# W032B.net
KiCad netlist of a schematic drawn in EAGLE
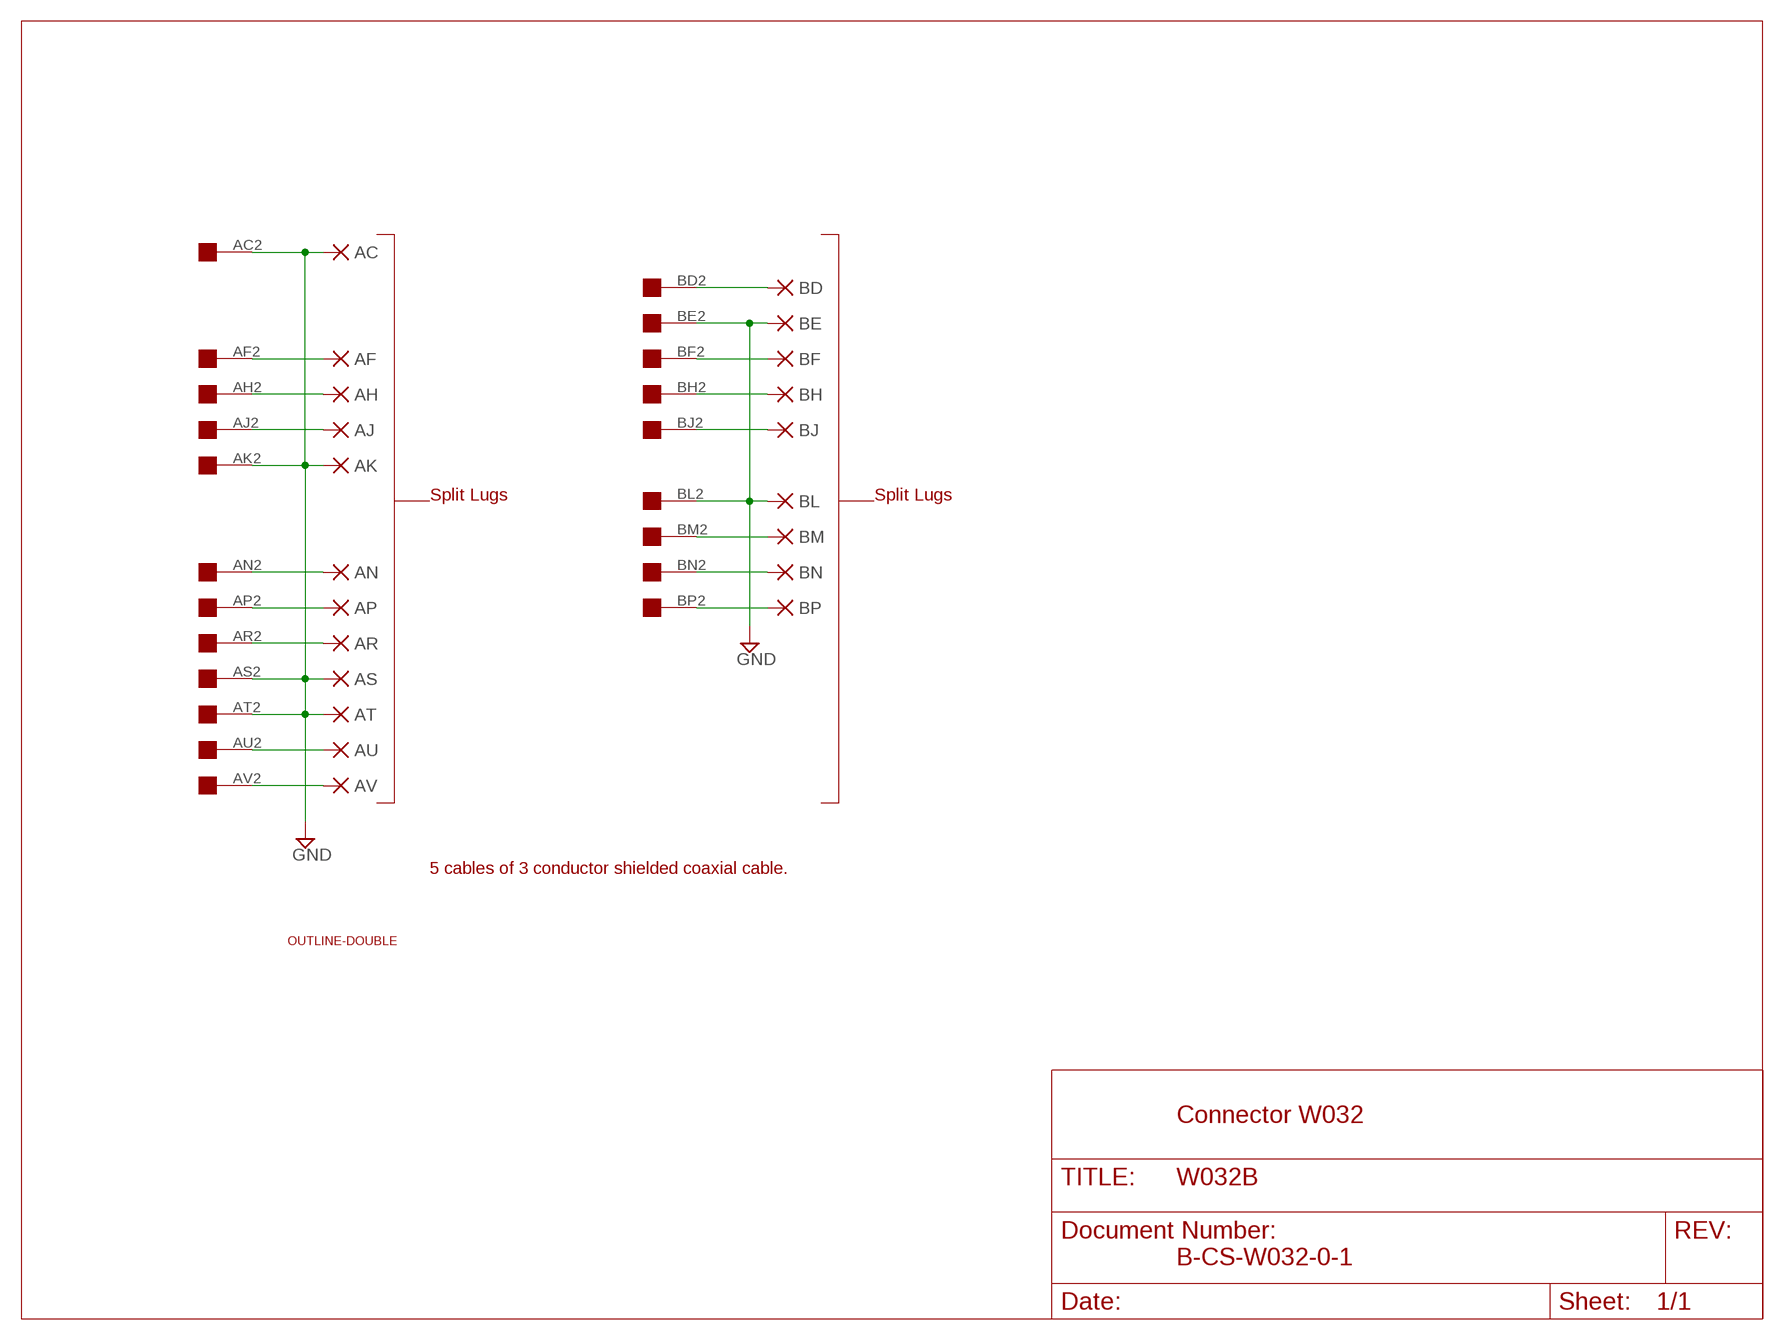
[diagram p0: schematic, sheet 1]

(export (version "E")
  (design (tool "Eeschema 10.0.6"))
  (components
    (comp (ref "AC")
      (value "PAD-0465")
      (footprint "eagle-import:0465")
      (libsource (lib "eagle-import") (part "PAD-0465"))
    )
    (comp (ref "AF")
      (value "PAD-0465")
      (footprint "eagle-import:0465")
      (libsource (lib "eagle-import") (part "PAD-0465"))
    )
    (comp (ref "AH")
      (value "PAD-0465")
      (footprint "eagle-import:0465")
      (libsource (lib "eagle-import") (part "PAD-0465"))
    )
    (comp (ref "AJ")
      (value "PAD-0465")
      (footprint "eagle-import:0465")
      (libsource (lib "eagle-import") (part "PAD-0465"))
    )
    (comp (ref "AK")
      (value "PAD-0465")
      (footprint "eagle-import:0465")
      (libsource (lib "eagle-import") (part "PAD-0465"))
    )
    (comp (ref "AN")
      (value "PAD-0465")
      (footprint "eagle-import:0465")
      (libsource (lib "eagle-import") (part "PAD-0465"))
    )
    (comp (ref "AP")
      (value "PAD-0465")
      (footprint "eagle-import:0465")
      (libsource (lib "eagle-import") (part "PAD-0465"))
    )
    (comp (ref "AR")
      (value "PAD-0465")
      (footprint "eagle-import:0465")
      (libsource (lib "eagle-import") (part "PAD-0465"))
    )
    (comp (ref "AS")
      (value "PAD-0465")
      (footprint "eagle-import:0465")
      (libsource (lib "eagle-import") (part "PAD-0465"))
    )
    (comp (ref "AT")
      (value "PAD-0465")
      (footprint "eagle-import:0465")
      (libsource (lib "eagle-import") (part "PAD-0465"))
    )
    (comp (ref "AU")
      (value "PAD-0465")
      (footprint "eagle-import:0465")
      (libsource (lib "eagle-import") (part "PAD-0465"))
    )
    (comp (ref "AV")
      (value "PAD-0465")
      (footprint "eagle-import:0465")
      (libsource (lib "eagle-import") (part "PAD-0465"))
    )
    (comp (ref "BD")
      (value "PAD-0465")
      (footprint "eagle-import:0465")
      (libsource (lib "eagle-import") (part "PAD-0465"))
    )
    (comp (ref "BE")
      (value "PAD-0465")
      (footprint "eagle-import:0465")
      (libsource (lib "eagle-import") (part "PAD-0465"))
    )
    (comp (ref "BF")
      (value "PAD-0465")
      (footprint "eagle-import:0465")
      (libsource (lib "eagle-import") (part "PAD-0465"))
    )
    (comp (ref "BH")
      (value "PAD-0465")
      (footprint "eagle-import:0465")
      (libsource (lib "eagle-import") (part "PAD-0465"))
    )
    (comp (ref "BJ")
      (value "PAD-0465")
      (footprint "eagle-import:0465")
      (libsource (lib "eagle-import") (part "PAD-0465"))
    )
    (comp (ref "BL")
      (value "PAD-0465")
      (footprint "eagle-import:0465")
      (libsource (lib "eagle-import") (part "PAD-0465"))
    )
    (comp (ref "BM")
      (value "PAD-0465")
      (footprint "eagle-import:0465")
      (libsource (lib "eagle-import") (part "PAD-0465"))
    )
    (comp (ref "BN")
      (value "PAD-0465")
      (footprint "eagle-import:0465")
      (libsource (lib "eagle-import") (part "PAD-0465"))
    )
    (comp (ref "BP")
      (value "PAD-0465")
      (footprint "eagle-import:0465")
      (libsource (lib "eagle-import") (part "PAD-0465"))
    )
    (comp (ref "U$1")
      (value "OUTLINE-DOUBLE")
      (footprint "eagle-import:DOUBLE")
      (libsource (lib "eagle-import") (part "OUTLINE-DOUBLE"))
    )
    (comp (ref "U$3")
      (value "DOUBLE")
      (footprint "eagle-import:EDGE-CON4")
      (libsource (lib "eagle-import") (part "DOUBLE"))
    )
  )
  (nets
    (net (code "1") (name "GND") (class "Default")
      (node (ref "AC") (pin "P$1") (pinfunction "P_P$1") (pintype "passive"))
      (node (ref "AK") (pin "P$1") (pinfunction "P_P$1") (pintype "passive"))
      (node (ref "AS") (pin "P$1") (pinfunction "P_P$1") (pintype "passive"))
      (node (ref "AT") (pin "P$1") (pinfunction "P_P$1") (pintype "passive"))
      (node (ref "BE") (pin "P$1") (pinfunction "P_P$1") (pintype "passive"))
      (node (ref "BL") (pin "P$1") (pinfunction "P_P$1") (pintype "passive"))
      (node (ref "U$3") (pin "AC2") (pinfunction "1_AC2") (pintype "bidirectional"))
      (node (ref "U$3") (pin "AK2") (pinfunction "1_AK2") (pintype "bidirectional"))
      (node (ref "U$3") (pin "AS2") (pinfunction "1_AS2") (pintype "bidirectional"))
      (node (ref "U$3") (pin "AT2") (pinfunction "1_AT2") (pintype "bidirectional"))
      (node (ref "U$3") (pin "BE2") (pinfunction "1_BE2") (pintype "bidirectional"))
      (node (ref "U$3") (pin "BL2") (pinfunction "1_BL2") (pintype "bidirectional"))
    )
    (net (code "2") (name "Net-(AF-P)") (class "Default")
      (node (ref "AF") (pin "P$1") (pinfunction "P_P$1") (pintype "passive"))
      (node (ref "U$3") (pin "AF2") (pinfunction "1_AF2") (pintype "bidirectional"))
    )
    (net (code "3") (name "Net-(AH-P)") (class "Default")
      (node (ref "AH") (pin "P$1") (pinfunction "P_P$1") (pintype "passive"))
      (node (ref "U$3") (pin "AH2") (pinfunction "1_AH2") (pintype "bidirectional"))
    )
    (net (code "4") (name "Net-(AJ-P)") (class "Default")
      (node (ref "AJ") (pin "P$1") (pinfunction "P_P$1") (pintype "passive"))
      (node (ref "U$3") (pin "AJ2") (pinfunction "1_AJ2") (pintype "bidirectional"))
    )
    (net (code "5") (name "Net-(AN-P)") (class "Default")
      (node (ref "AN") (pin "P$1") (pinfunction "P_P$1") (pintype "passive"))
      (node (ref "U$3") (pin "AN2") (pinfunction "1_AN2") (pintype "bidirectional"))
    )
    (net (code "6") (name "Net-(AP-P)") (class "Default")
      (node (ref "AP") (pin "P$1") (pinfunction "P_P$1") (pintype "passive"))
      (node (ref "U$3") (pin "AP2") (pinfunction "1_AP2") (pintype "bidirectional"))
    )
    (net (code "7") (name "Net-(AR-P)") (class "Default")
      (node (ref "AR") (pin "P$1") (pinfunction "P_P$1") (pintype "passive"))
      (node (ref "U$3") (pin "AR2") (pinfunction "1_AR2") (pintype "bidirectional"))
    )
    (net (code "8") (name "Net-(AU-P)") (class "Default")
      (node (ref "AU") (pin "P$1") (pinfunction "P_P$1") (pintype "passive"))
      (node (ref "U$3") (pin "AU2") (pinfunction "1_AU2") (pintype "bidirectional"))
    )
    (net (code "9") (name "Net-(AV-P)") (class "Default")
      (node (ref "AV") (pin "P$1") (pinfunction "P_P$1") (pintype "passive"))
      (node (ref "U$3") (pin "AV2") (pinfunction "1_AV2") (pintype "bidirectional"))
    )
    (net (code "10") (name "Net-(BD-P)") (class "Default")
      (node (ref "BD") (pin "P$1") (pinfunction "P_P$1") (pintype "passive"))
      (node (ref "U$3") (pin "BD2") (pinfunction "1_BD2") (pintype "bidirectional"))
    )
    (net (code "11") (name "Net-(BF-P)") (class "Default")
      (node (ref "BF") (pin "P$1") (pinfunction "P_P$1") (pintype "passive"))
      (node (ref "U$3") (pin "BF2") (pinfunction "1_BF2") (pintype "bidirectional"))
    )
    (net (code "12") (name "Net-(BH-P)") (class "Default")
      (node (ref "BH") (pin "P$1") (pinfunction "P_P$1") (pintype "passive"))
      (node (ref "U$3") (pin "BH2") (pinfunction "1_BH2") (pintype "bidirectional"))
    )
    (net (code "13") (name "Net-(BJ-P)") (class "Default")
      (node (ref "BJ") (pin "P$1") (pinfunction "P_P$1") (pintype "passive"))
      (node (ref "U$3") (pin "BJ2") (pinfunction "1_BJ2") (pintype "bidirectional"))
    )
    (net (code "14") (name "Net-(BM-P)") (class "Default")
      (node (ref "BM") (pin "P$1") (pinfunction "P_P$1") (pintype "passive"))
      (node (ref "U$3") (pin "BM2") (pinfunction "1_BM2") (pintype "bidirectional"))
    )
    (net (code "15") (name "Net-(BN-P)") (class "Default")
      (node (ref "BN") (pin "P$1") (pinfunction "P_P$1") (pintype "passive"))
      (node (ref "U$3") (pin "BN2") (pinfunction "1_BN2") (pintype "bidirectional"))
    )
    (net (code "16") (name "Net-(BP-P)") (class "Default")
      (node (ref "BP") (pin "P$1") (pinfunction "P_P$1") (pintype "passive"))
      (node (ref "U$3") (pin "BP2") (pinfunction "1_BP2") (pintype "bidirectional"))
    )
  )
)
